# 2ndNov_submission_12V_everywhere.net
KiCad netlist of a schematic drawn in EAGLE
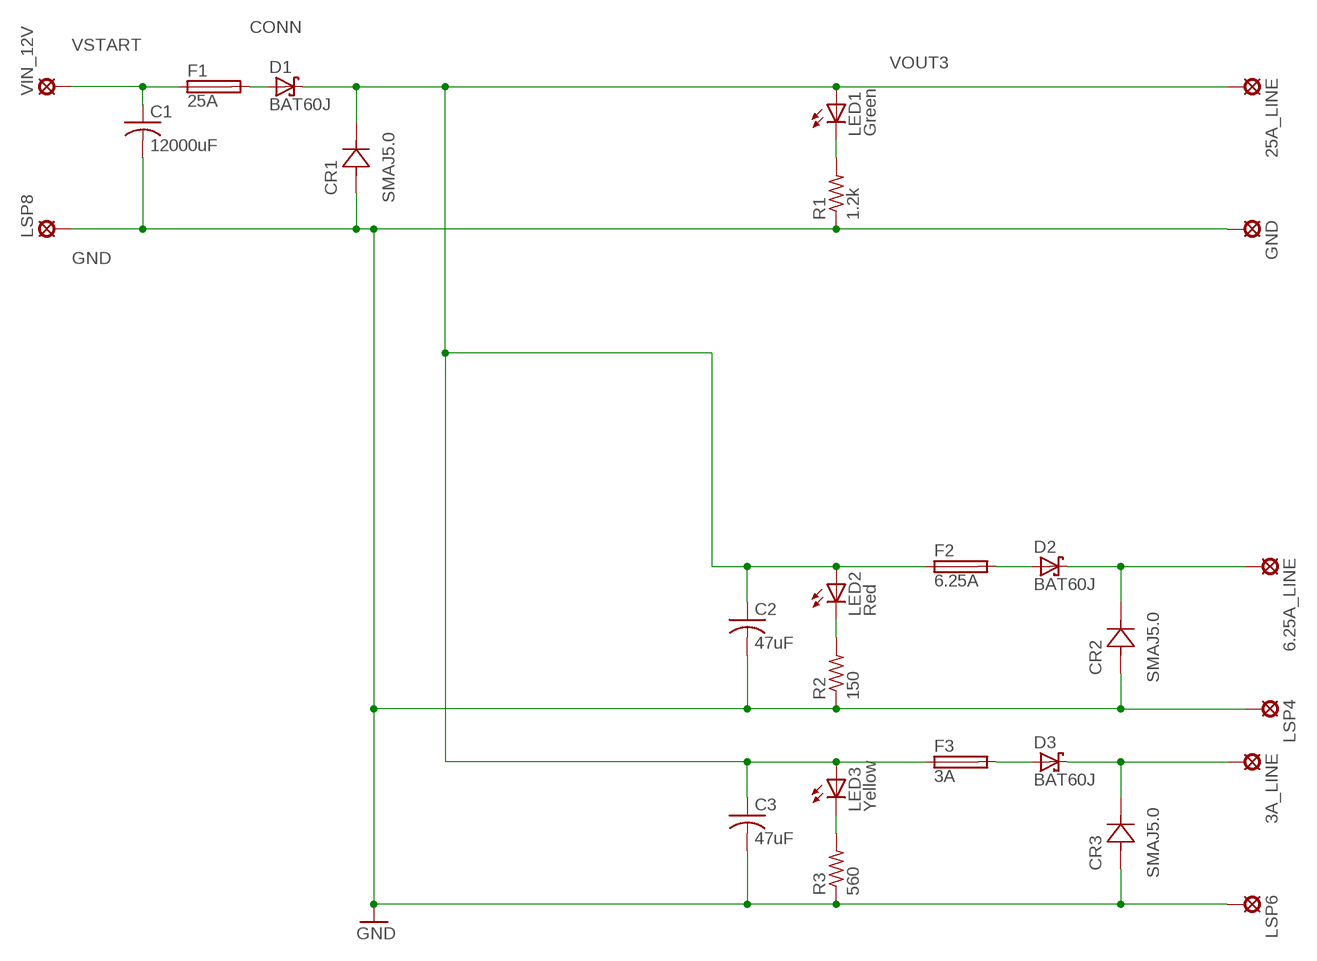
[diagram p0: schematic, sheet 1]

(export (version "E")
  (design (tool "Eeschema 10.0.6"))
  (components
    (comp (ref "3A_LINE")
      (value "SE13")
      (footprint "eagle-import:SE13")
      (libsource (lib "eagle-import") (part "SE13"))
    )
    (comp (ref "6.25A_LINE")
      (value "SE13")
      (footprint "eagle-import:SE13")
      (libsource (lib "eagle-import") (part "SE13"))
    )
    (comp (ref "25A_LINE")
      (value "SE13")
      (footprint "eagle-import:SE13")
      (libsource (lib "eagle-import") (part "SE13"))
    )
    (comp (ref "C1")
      (value "12000uF")
      (footprint "eagle-import:C1206K")
      (libsource (lib "eagle-import") (part "C-USC1206K"))
    )
    (comp (ref "C2")
      (value "47uF")
      (footprint "eagle-import:C1206K")
      (libsource (lib "eagle-import") (part "C-USC1206K"))
    )
    (comp (ref "C3")
      (value "47uF")
      (footprint "eagle-import:C1206K")
      (libsource (lib "eagle-import") (part "C-USC1206K"))
    )
    (comp (ref "CR1")
      (value "SMAJ5.0")
      (footprint "eagle-import:SMASERIES")
      (libsource (lib "eagle-import") (part "SMAJ5.0"))
    )
    (comp (ref "CR2")
      (value "SMAJ5.0")
      (footprint "eagle-import:SMASERIES")
      (libsource (lib "eagle-import") (part "SMAJ5.0"))
    )
    (comp (ref "CR3")
      (value "SMAJ5.0")
      (footprint "eagle-import:SMASERIES")
      (libsource (lib "eagle-import") (part "SMAJ5.0"))
    )
    (comp (ref "D1")
      (value "BAT60J")
      (footprint "eagle-import:SOD323_ST")
      (libsource (lib "eagle-import") (part "BAT60J"))
    )
    (comp (ref "D2")
      (value "BAT60J")
      (footprint "eagle-import:SOD323_ST")
      (libsource (lib "eagle-import") (part "BAT60J"))
    )
    (comp (ref "D3")
      (value "BAT60J")
      (footprint "eagle-import:SOD323_ST")
      (libsource (lib "eagle-import") (part "BAT60J"))
    )
    (comp (ref "F1")
      (value "25A")
      (footprint "eagle-import:TE5")
      (libsource (lib "eagle-import") (part "TE5"))
    )
    (comp (ref "F2")
      (value "6.25A")
      (footprint "eagle-import:TE5")
      (libsource (lib "eagle-import") (part "TE5"))
    )
    (comp (ref "F3")
      (value "3A")
      (footprint "eagle-import:TE5")
      (libsource (lib "eagle-import") (part "TE5"))
    )
    (comp (ref "GND")
      (value "SE13")
      (footprint "eagle-import:SE13")
      (libsource (lib "eagle-import") (part "SE13"))
    )
    (comp (ref "LED1")
      (value "Green")
      (footprint "eagle-import:CHIPLED_1206")
      (libsource (lib "eagle-import") (part "LEDCHIPLED_1206"))
    )
    (comp (ref "LED2")
      (value "Red")
      (footprint "eagle-import:CHIPLED_1206")
      (libsource (lib "eagle-import") (part "LEDCHIPLED_1206"))
    )
    (comp (ref "LED3")
      (value "Yellow")
      (footprint "eagle-import:CHIPLED_1206")
      (libsource (lib "eagle-import") (part "LEDCHIPLED_1206"))
    )
    (comp (ref "LSP4")
      (value "SE13")
      (footprint "eagle-import:SE13")
      (libsource (lib "eagle-import") (part "SE13"))
    )
    (comp (ref "LSP6")
      (value "SE13")
      (footprint "eagle-import:SE13")
      (libsource (lib "eagle-import") (part "SE13"))
    )
    (comp (ref "LSP8")
      (value "SE13")
      (footprint "eagle-import:SE13")
      (libsource (lib "eagle-import") (part "SE13"))
    )
    (comp (ref "R1")
      (value "1.2k")
      (footprint "eagle-import:R1206")
      (libsource (lib "eagle-import") (part "R-US_R1206"))
    )
    (comp (ref "R2")
      (value "150")
      (footprint "eagle-import:R1206")
      (libsource (lib "eagle-import") (part "R-US_R1206"))
    )
    (comp (ref "R3")
      (value "560")
      (footprint "eagle-import:R1206")
      (libsource (lib "eagle-import") (part "R-US_R1206"))
    )
    (comp (ref "VIN_12V")
      (value "SE13")
      (footprint "eagle-import:SE13")
      (libsource (lib "eagle-import") (part "SE13"))
    )
  )
  (nets
    (net (code "1") (name "/CONN") (class "Default")
      (node (ref "D1") (pin "A") (pinfunction "A_A") (pintype "passive"))
      (node (ref "F1") (pin "2") (pinfunction "2_2") (pintype "passive"))
    )
    (net (code "2") (name "/VOUT3") (class "Default")
      (node (ref "25A_LINE") (pin "MP") (pinfunction "MP_MP") (pintype "passive"))
      (node (ref "C2") (pin "1") (pinfunction "1_1") (pintype "passive"))
      (node (ref "C3") (pin "1") (pinfunction "1_1") (pintype "passive"))
      (node (ref "CR1") (pin "1") (pinfunction "2_1") (pintype "passive"))
      (node (ref "D1") (pin "C") (pinfunction "C_C") (pintype "passive"))
      (node (ref "F2") (pin "1") (pinfunction "1_1") (pintype "passive"))
      (node (ref "F3") (pin "1") (pinfunction "1_1") (pintype "passive"))
      (node (ref "LED1") (pin "A") (pinfunction "A_A") (pintype "passive"))
      (node (ref "LED2") (pin "A") (pinfunction "A_A") (pintype "passive"))
      (node (ref "LED3") (pin "A") (pinfunction "A_A") (pintype "passive"))
    )
    (net (code "3") (name "/VSTART") (class "Default")
      (node (ref "C1") (pin "1") (pinfunction "1_1") (pintype "passive"))
      (node (ref "F1") (pin "1") (pinfunction "1_1") (pintype "passive"))
      (node (ref "VIN_12V") (pin "MP") (pinfunction "MP_MP") (pintype "passive"))
    )
    (net (code "4") (name "GND") (class "Default")
      (node (ref "C1") (pin "2") (pinfunction "2_2") (pintype "passive"))
      (node (ref "C2") (pin "2") (pinfunction "2_2") (pintype "passive"))
      (node (ref "C3") (pin "2") (pinfunction "2_2") (pintype "passive"))
      (node (ref "CR1") (pin "2") (pinfunction "1_2") (pintype "passive"))
      (node (ref "CR2") (pin "2") (pinfunction "1_2") (pintype "passive"))
      (node (ref "CR3") (pin "2") (pinfunction "1_2") (pintype "passive"))
      (node (ref "GND") (pin "MP") (pinfunction "MP_MP") (pintype "passive"))
      (node (ref "LSP4") (pin "MP") (pinfunction "MP_MP") (pintype "passive"))
      (node (ref "LSP6") (pin "MP") (pinfunction "MP_MP") (pintype "passive"))
      (node (ref "LSP8") (pin "MP") (pinfunction "MP_MP") (pintype "passive"))
      (node (ref "R1") (pin "1") (pinfunction "1_1") (pintype "passive"))
      (node (ref "R2") (pin "1") (pinfunction "1_1") (pintype "passive"))
      (node (ref "R3") (pin "1") (pinfunction "1_1") (pintype "passive"))
    )
    (net (code "5") (name "Net-(CR2-2)") (class "Default")
      (node (ref "6.25A_LINE") (pin "MP") (pinfunction "MP_MP") (pintype "passive"))
      (node (ref "CR2") (pin "1") (pinfunction "2_1") (pintype "passive"))
      (node (ref "D2") (pin "C") (pinfunction "C_C") (pintype "passive"))
    )
    (net (code "6") (name "Net-(CR3-2)") (class "Default")
      (node (ref "3A_LINE") (pin "MP") (pinfunction "MP_MP") (pintype "passive"))
      (node (ref "CR3") (pin "1") (pinfunction "2_1") (pintype "passive"))
      (node (ref "D3") (pin "C") (pinfunction "C_C") (pintype "passive"))
    )
    (net (code "7") (name "Net-(D2-PadA)") (class "Default")
      (node (ref "D2") (pin "A") (pinfunction "A_A") (pintype "passive"))
      (node (ref "F2") (pin "2") (pinfunction "2_2") (pintype "passive"))
    )
    (net (code "8") (name "Net-(D3-PadA)") (class "Default")
      (node (ref "D3") (pin "A") (pinfunction "A_A") (pintype "passive"))
      (node (ref "F3") (pin "2") (pinfunction "2_2") (pintype "passive"))
    )
    (net (code "9") (name "Net-(LED1-PadC)") (class "Default")
      (node (ref "LED1") (pin "C") (pinfunction "C_C") (pintype "passive"))
      (node (ref "R1") (pin "2") (pinfunction "2_2") (pintype "passive"))
    )
    (net (code "10") (name "Net-(LED2-PadC)") (class "Default")
      (node (ref "LED2") (pin "C") (pinfunction "C_C") (pintype "passive"))
      (node (ref "R2") (pin "2") (pinfunction "2_2") (pintype "passive"))
    )
    (net (code "11") (name "Net-(LED3-PadC)") (class "Default")
      (node (ref "LED3") (pin "C") (pinfunction "C_C") (pintype "passive"))
      (node (ref "R3") (pin "2") (pinfunction "2_2") (pintype "passive"))
    )
  )
)
